# vme_can_vme_2.net
KiCad netlist of a schematic drawn in Altium Designer
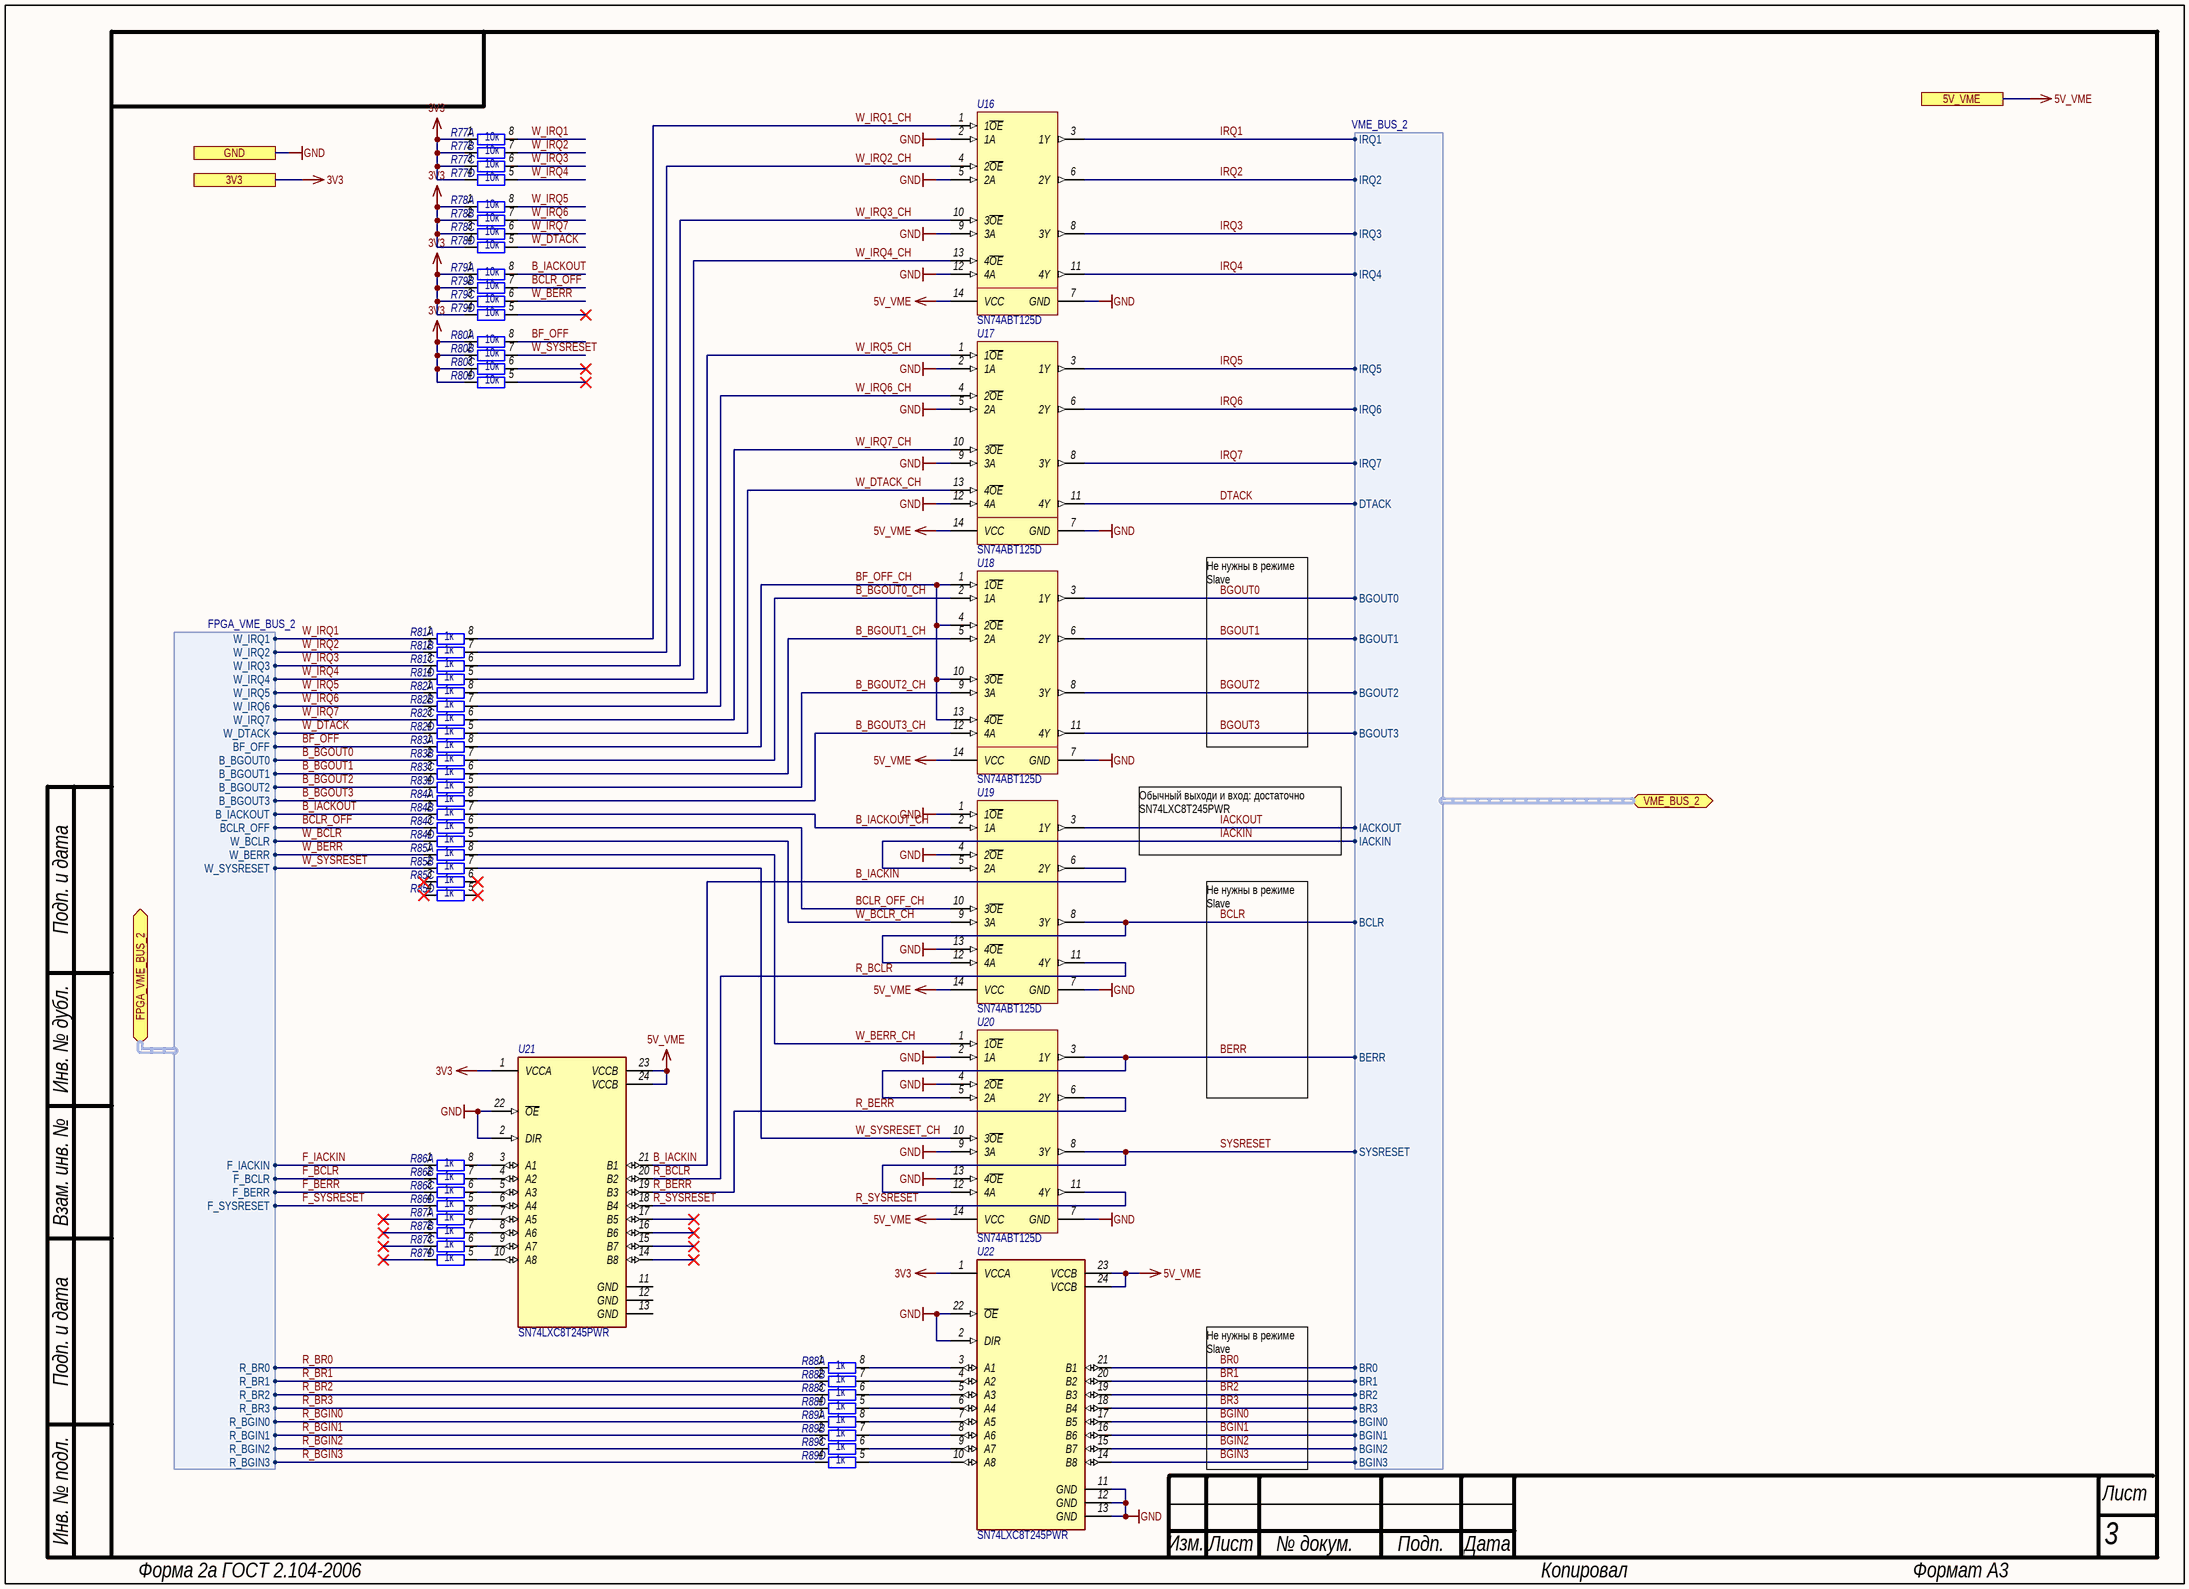
[diagram p0: vme_can_vme_2.SchDoc]

(export (version "E")
  (design (tool "Eeschema 10.0.6"))
  (components
    (comp (ref "R77")
      (value "10к")
      (footprint "TC124")
      (description "4 Chip Resistor Array")
      (libsource (lib "Passive") (part "Resistor-4"))
    )
    (comp (ref "R78")
      (value "10к")
      (footprint "TC124")
      (description "4 Chip Resistor Array")
      (libsource (lib "Passive") (part "Resistor-4"))
    )
    (comp (ref "R79")
      (value "10к")
      (footprint "TC124")
      (description "4 Chip Resistor Array")
      (libsource (lib "Passive") (part "Resistor-4"))
    )
    (comp (ref "R80")
      (value "10к")
      (footprint "TC124")
      (description "4 Chip Resistor Array")
      (libsource (lib "Passive") (part "Resistor-4"))
    )
    (comp (ref "R81")
      (value "1к")
      (footprint "TC124")
      (description "4 Chip Resistor Array")
      (libsource (lib "Passive") (part "Resistor-4"))
    )
    (comp (ref "R82")
      (value "1к")
      (footprint "TC124")
      (description "4 Chip Resistor Array")
      (libsource (lib "Passive") (part "Resistor-4"))
    )
    (comp (ref "R83")
      (value "1к")
      (footprint "TC124")
      (description "4 Chip Resistor Array")
      (libsource (lib "Passive") (part "Resistor-4"))
    )
    (comp (ref "R84")
      (value "1к")
      (footprint "TC124")
      (description "4 Chip Resistor Array")
      (libsource (lib "Passive") (part "Resistor-4"))
    )
    (comp (ref "R85")
      (value "1к")
      (footprint "TC124")
      (description "4 Chip Resistor Array")
      (libsource (lib "Passive") (part "Resistor-4"))
    )
    (comp (ref "R86")
      (value "1к")
      (footprint "TC124")
      (description "4 Chip Resistor Array")
      (libsource (lib "Passive") (part "Resistor-4"))
    )
    (comp (ref "R87")
      (value "1к")
      (footprint "TC124")
      (description "4 Chip Resistor Array")
      (libsource (lib "Passive") (part "Resistor-4"))
    )
    (comp (ref "R88")
      (value "1к")
      (footprint "TC124")
      (description "4 Chip Resistor Array")
      (libsource (lib "Passive") (part "Resistor-4"))
    )
    (comp (ref "R89")
      (value "1к")
      (footprint "TC124")
      (description "4 Chip Resistor Array")
      (libsource (lib "Passive") (part "Resistor-4"))
    )
    (comp (ref "U16")
      (value "SN74ABT125D")
      (footprint "SOIC-14")
      (description "QUADRUPLE BUS BUFFER GATES")
      (fields (field (name "НАИМЕНОВАНИЕ") "SN74ABT125D"))
      (libsource (lib "Transceiver") (part "SN74ABT125D"))
    )
    (comp (ref "U17")
      (value "SN74ABT125D")
      (footprint "SOIC-14")
      (description "QUADRUPLE BUS BUFFER GATES")
      (fields (field (name "НАИМЕНОВАНИЕ") "SN74ABT125D"))
      (libsource (lib "Transceiver") (part "SN74ABT125D"))
    )
    (comp (ref "U18")
      (value "SN74ABT125D")
      (footprint "SOIC-14")
      (description "QUADRUPLE BUS BUFFER GATES")
      (fields (field (name "НАИМЕНОВАНИЕ") "SN74ABT125D"))
      (libsource (lib "Transceiver") (part "SN74ABT125D"))
    )
    (comp (ref "U19")
      (value "SN74ABT125D")
      (footprint "SOIC-14")
      (description "QUADRUPLE BUS BUFFER GATES")
      (fields (field (name "НАИМЕНОВАНИЕ") "SN74ABT125D"))
      (libsource (lib "Transceiver") (part "SN74ABT125D"))
    )
    (comp (ref "U20")
      (value "SN74ABT125D")
      (footprint "SOIC-14")
      (description "QUADRUPLE BUS BUFFER GATES")
      (fields (field (name "НАИМЕНОВАНИЕ") "SN74ABT125D"))
      (libsource (lib "Transceiver") (part "SN74ABT125D"))
    )
    (comp (ref "U21")
      (value "SN74LXC8T245PWR")
      (footprint "TSSOP-24")
      (description "Dual-Supply Bus Transceiver with Configurable Level Shifting\r\nand 3-State Outputs")
      (fields (field (name "НАИМЕНОВАНИЕ") "SN74LXC8T245PWR"))
      (libsource (lib "Transceiver") (part "SN74LXC8T245PWR"))
    )
    (comp (ref "U22")
      (value "SN74LXC8T245PWR")
      (footprint "TSSOP-24")
      (description "Dual-Supply Bus Transceiver with Configurable Level Shifting\r\nand 3-State Outputs")
      (fields (field (name "НАИМЕНОВАНИЕ") "SN74LXC8T245PWR"))
      (libsource (lib "Transceiver") (part "SN74LXC8T245PWR"))
    )
  )
  (nets
    (net (code "3") (name "/BCLR") (class "Default")
      (node (ref "U19") (pin "12") (pinfunction "4A_12") (pintype "input"))
      (node (ref "U19") (pin "8") (pinfunction "3Y_8") (pintype "output"))
    )
    (net (code "4") (name "/BCLR_OFF") (class "Default")
      (node (ref "R79") (pin "7") (pinfunction "7_7") (pintype "passive"))
      (node (ref "R84") (pin "3") (pinfunction "3_3") (pintype "passive"))
    )
    (net (code "5") (name "/BCLR_OFF_CH") (class "Default")
      (node (ref "R84") (pin "6") (pinfunction "6_6") (pintype "passive"))
      (node (ref "U19") (pin "10") (pinfunction "3~{OE}_10") (pintype "input"))
    )
    (net (code "6") (name "/BERR") (class "Default")
      (node (ref "U20") (pin "3") (pinfunction "1Y_3") (pintype "output"))
      (node (ref "U20") (pin "5") (pinfunction "2A_5") (pintype "input"))
    )
    (net (code "7") (name "/BF_OFF") (class "Default")
      (node (ref "R80") (pin "8") (pinfunction "8_8") (pintype "passive"))
      (node (ref "R83") (pin "1") (pinfunction "1_1") (pintype "passive"))
    )
    (net (code "8") (name "/BF_OFF_CH") (class "Default")
      (node (ref "R83") (pin "8") (pinfunction "8_8") (pintype "passive"))
      (node (ref "U18") (pin "1") (pinfunction "1~{OE}_1") (pintype "input"))
      (node (ref "U18") (pin "10") (pinfunction "3~{OE}_10") (pintype "input"))
      (node (ref "U18") (pin "13") (pinfunction "4~{OE}_13") (pintype "input"))
      (node (ref "U18") (pin "4") (pinfunction "2~{OE}_4") (pintype "input"))
    )
    (net (code "9") (name "/BGIN0") (class "Default")
      (node (ref "U22") (pin "17") (pinfunction "B5_17") (pintype "bidirectional"))
    )
    (net (code "10") (name "/BGIN1") (class "Default")
      (node (ref "U22") (pin "16") (pinfunction "B6_16") (pintype "bidirectional"))
    )
    (net (code "11") (name "/BGIN2") (class "Default")
      (node (ref "U22") (pin "15") (pinfunction "B7_15") (pintype "bidirectional"))
    )
    (net (code "12") (name "/BGIN3") (class "Default")
      (node (ref "U22") (pin "14") (pinfunction "B8_14") (pintype "bidirectional"))
    )
    (net (code "13") (name "/BGOUT0") (class "Default")
      (node (ref "U18") (pin "3") (pinfunction "1Y_3") (pintype "output"))
    )
    (net (code "14") (name "/BGOUT1") (class "Default")
      (node (ref "U18") (pin "6") (pinfunction "2Y_6") (pintype "output"))
    )
    (net (code "15") (name "/BGOUT2") (class "Default")
      (node (ref "U18") (pin "8") (pinfunction "3Y_8") (pintype "output"))
    )
    (net (code "16") (name "/BGOUT3") (class "Default")
      (node (ref "U18") (pin "11") (pinfunction "4Y_11") (pintype "output"))
    )
    (net (code "17") (name "/BR0") (class "Default")
      (node (ref "U22") (pin "21") (pinfunction "B1_21") (pintype "bidirectional"))
    )
    (net (code "18") (name "/BR1") (class "Default")
      (node (ref "U22") (pin "20") (pinfunction "B2_20") (pintype "bidirectional"))
    )
    (net (code "19") (name "/BR2") (class "Default")
      (node (ref "U22") (pin "19") (pinfunction "B3_19") (pintype "bidirectional"))
    )
    (net (code "20") (name "/BR3") (class "Default")
      (node (ref "U22") (pin "18") (pinfunction "B4_18") (pintype "bidirectional"))
    )
    (net (code "21") (name "/B_BGOUT0") (class "Default")
      (node (ref "R83") (pin "2") (pinfunction "2_2") (pintype "passive"))
    )
    (net (code "22") (name "/B_BGOUT0_CH") (class "Default")
      (node (ref "R83") (pin "7") (pinfunction "7_7") (pintype "passive"))
      (node (ref "U18") (pin "2") (pinfunction "1A_2") (pintype "input"))
    )
    (net (code "23") (name "/B_BGOUT1") (class "Default")
      (node (ref "R83") (pin "3") (pinfunction "3_3") (pintype "passive"))
    )
    (net (code "24") (name "/B_BGOUT1_CH") (class "Default")
      (node (ref "R83") (pin "6") (pinfunction "6_6") (pintype "passive"))
      (node (ref "U18") (pin "5") (pinfunction "2A_5") (pintype "input"))
    )
    (net (code "25") (name "/B_BGOUT2") (class "Default")
      (node (ref "R83") (pin "4") (pinfunction "4_4") (pintype "passive"))
    )
    (net (code "26") (name "/B_BGOUT2_CH") (class "Default")
      (node (ref "R83") (pin "5") (pinfunction "5_5") (pintype "passive"))
      (node (ref "U18") (pin "9") (pinfunction "3A_9") (pintype "input"))
    )
    (net (code "27") (name "/B_BGOUT3") (class "Default")
      (node (ref "R84") (pin "1") (pinfunction "1_1") (pintype "passive"))
    )
    (net (code "28") (name "/B_BGOUT3_CH") (class "Default")
      (node (ref "R84") (pin "8") (pinfunction "8_8") (pintype "passive"))
      (node (ref "U18") (pin "12") (pinfunction "4A_12") (pintype "input"))
    )
    (net (code "29") (name "/B_IACKIN") (class "Default")
      (node (ref "U19") (pin "6") (pinfunction "2Y_6") (pintype "output"))
      (node (ref "U21") (pin "21") (pinfunction "B1_21") (pintype "bidirectional"))
    )
    (net (code "30") (name "/B_IACKOUT") (class "Default")
      (node (ref "R79") (pin "8") (pinfunction "8_8") (pintype "passive"))
      (node (ref "R84") (pin "2") (pinfunction "2_2") (pintype "passive"))
    )
    (net (code "31") (name "/B_IACKOUT_CH") (class "Default")
      (node (ref "R84") (pin "7") (pinfunction "7_7") (pintype "passive"))
      (node (ref "U19") (pin "2") (pinfunction "1A_2") (pintype "input"))
    )
    (net (code "32") (name "/DTACK") (class "Default")
      (node (ref "U17") (pin "11") (pinfunction "4Y_11") (pintype "output"))
    )
    (net (code "33") (name "/F_BCLR") (class "Default")
      (node (ref "R86") (pin "2") (pinfunction "2_2") (pintype "passive"))
    )
    (net (code "34") (name "/F_BERR") (class "Default")
      (node (ref "R86") (pin "3") (pinfunction "3_3") (pintype "passive"))
    )
    (net (code "35") (name "/F_IACKIN") (class "Default")
      (node (ref "R86") (pin "1") (pinfunction "1_1") (pintype "passive"))
    )
    (net (code "36") (name "/F_SYSRESET") (class "Default")
      (node (ref "R86") (pin "4") (pinfunction "4_4") (pintype "passive"))
    )
    (net (code "37") (name "/IACKIN") (class "Default")
      (node (ref "U19") (pin "5") (pinfunction "2A_5") (pintype "input"))
    )
    (net (code "38") (name "/IACKOUT") (class "Default")
      (node (ref "U19") (pin "3") (pinfunction "1Y_3") (pintype "output"))
    )
    (net (code "39") (name "/IRQ1") (class "Default")
      (node (ref "U16") (pin "3") (pinfunction "1Y_3") (pintype "output"))
    )
    (net (code "40") (name "/IRQ2") (class "Default")
      (node (ref "U16") (pin "6") (pinfunction "2Y_6") (pintype "output"))
    )
    (net (code "41") (name "/IRQ3") (class "Default")
      (node (ref "U16") (pin "8") (pinfunction "3Y_8") (pintype "output"))
    )
    (net (code "42") (name "/IRQ4") (class "Default")
      (node (ref "U16") (pin "11") (pinfunction "4Y_11") (pintype "output"))
    )
    (net (code "43") (name "/IRQ5") (class "Default")
      (node (ref "U17") (pin "3") (pinfunction "1Y_3") (pintype "output"))
    )
    (net (code "44") (name "/IRQ6") (class "Default")
      (node (ref "U17") (pin "6") (pinfunction "2Y_6") (pintype "output"))
    )
    (net (code "45") (name "/IRQ7") (class "Default")
      (node (ref "U17") (pin "8") (pinfunction "3Y_8") (pintype "output"))
    )
    (net (code "46") (name "/R_BCLR") (class "Default")
      (node (ref "U19") (pin "11") (pinfunction "4Y_11") (pintype "output"))
      (node (ref "U21") (pin "20") (pinfunction "B2_20") (pintype "bidirectional"))
    )
    (net (code "47") (name "/R_BERR") (class "Default")
      (node (ref "U20") (pin "6") (pinfunction "2Y_6") (pintype "output"))
      (node (ref "U21") (pin "19") (pinfunction "B3_19") (pintype "bidirectional"))
    )
    (net (code "48") (name "/R_BGIN0") (class "Default")
      (node (ref "R89") (pin "1") (pinfunction "1_1") (pintype "passive"))
    )
    (net (code "49") (name "/R_BGIN1") (class "Default")
      (node (ref "R89") (pin "2") (pinfunction "2_2") (pintype "passive"))
    )
    (net (code "50") (name "/R_BGIN2") (class "Default")
      (node (ref "R89") (pin "3") (pinfunction "3_3") (pintype "passive"))
    )
    (net (code "51") (name "/R_BGIN3") (class "Default")
      (node (ref "R89") (pin "4") (pinfunction "4_4") (pintype "passive"))
    )
    (net (code "52") (name "/R_BR0") (class "Default")
      (node (ref "R88") (pin "1") (pinfunction "1_1") (pintype "passive"))
    )
    (net (code "53") (name "/R_BR1") (class "Default")
      (node (ref "R88") (pin "2") (pinfunction "2_2") (pintype "passive"))
    )
    (net (code "54") (name "/R_BR2") (class "Default")
      (node (ref "R88") (pin "3") (pinfunction "3_3") (pintype "passive"))
    )
    (net (code "55") (name "/R_BR3") (class "Default")
      (node (ref "R88") (pin "4") (pinfunction "4_4") (pintype "passive"))
    )
    (net (code "56") (name "/R_SYSRESET") (class "Default")
      (node (ref "U20") (pin "11") (pinfunction "4Y_11") (pintype "output"))
      (node (ref "U21") (pin "18") (pinfunction "B4_18") (pintype "bidirectional"))
    )
    (net (code "57") (name "/SYSRESET") (class "Default")
      (node (ref "U20") (pin "12") (pinfunction "4A_12") (pintype "input"))
      (node (ref "U20") (pin "8") (pinfunction "3Y_8") (pintype "output"))
    )
    (net (code "58") (name "/W_BCLR") (class "Default")
      (node (ref "R84") (pin "4") (pinfunction "4_4") (pintype "passive"))
    )
    (net (code "59") (name "/W_BCLR_CH") (class "Default")
      (node (ref "R84") (pin "5") (pinfunction "5_5") (pintype "passive"))
      (node (ref "U19") (pin "9") (pinfunction "3A_9") (pintype "input"))
    )
    (net (code "60") (name "/W_BERR") (class "Default")
      (node (ref "R79") (pin "6") (pinfunction "6_6") (pintype "passive"))
      (node (ref "R85") (pin "1") (pinfunction "1_1") (pintype "passive"))
    )
    (net (code "61") (name "/W_BERR_CH") (class "Default")
      (node (ref "R85") (pin "8") (pinfunction "8_8") (pintype "passive"))
      (node (ref "U20") (pin "1") (pinfunction "1~{OE}_1") (pintype "input"))
    )
    (net (code "62") (name "/W_DTACK") (class "Default")
      (node (ref "R78") (pin "5") (pinfunction "5_5") (pintype "passive"))
      (node (ref "R82") (pin "4") (pinfunction "4_4") (pintype "passive"))
    )
    (net (code "63") (name "/W_DTACK_CH") (class "Default")
      (node (ref "R82") (pin "5") (pinfunction "5_5") (pintype "passive"))
      (node (ref "U17") (pin "13") (pinfunction "4~{OE}_13") (pintype "input"))
    )
    (net (code "64") (name "/W_IRQ1") (class "Default")
      (node (ref "R77") (pin "8") (pinfunction "8_8") (pintype "passive"))
      (node (ref "R81") (pin "1") (pinfunction "1_1") (pintype "passive"))
    )
    (net (code "65") (name "/W_IRQ1_CH") (class "Default")
      (node (ref "R81") (pin "8") (pinfunction "8_8") (pintype "passive"))
      (node (ref "U16") (pin "1") (pinfunction "1~{OE}_1") (pintype "input"))
    )
    (net (code "66") (name "/W_IRQ2") (class "Default")
      (node (ref "R77") (pin "7") (pinfunction "7_7") (pintype "passive"))
      (node (ref "R81") (pin "2") (pinfunction "2_2") (pintype "passive"))
    )
    (net (code "67") (name "/W_IRQ2_CH") (class "Default")
      (node (ref "R81") (pin "7") (pinfunction "7_7") (pintype "passive"))
      (node (ref "U16") (pin "4") (pinfunction "2~{OE}_4") (pintype "input"))
    )
    (net (code "68") (name "/W_IRQ3") (class "Default")
      (node (ref "R77") (pin "6") (pinfunction "6_6") (pintype "passive"))
      (node (ref "R81") (pin "3") (pinfunction "3_3") (pintype "passive"))
    )
    (net (code "69") (name "/W_IRQ3_CH") (class "Default")
      (node (ref "R81") (pin "6") (pinfunction "6_6") (pintype "passive"))
      (node (ref "U16") (pin "10") (pinfunction "3~{OE}_10") (pintype "input"))
    )
    (net (code "70") (name "/W_IRQ4") (class "Default")
      (node (ref "R77") (pin "5") (pinfunction "5_5") (pintype "passive"))
      (node (ref "R81") (pin "4") (pinfunction "4_4") (pintype "passive"))
    )
    (net (code "71") (name "/W_IRQ4_CH") (class "Default")
      (node (ref "R81") (pin "5") (pinfunction "5_5") (pintype "passive"))
      (node (ref "U16") (pin "13") (pinfunction "4~{OE}_13") (pintype "input"))
    )
    (net (code "72") (name "/W_IRQ5") (class "Default")
      (node (ref "R78") (pin "8") (pinfunction "8_8") (pintype "passive"))
      (node (ref "R82") (pin "1") (pinfunction "1_1") (pintype "passive"))
    )
    (net (code "73") (name "/W_IRQ5_CH") (class "Default")
      (node (ref "R82") (pin "8") (pinfunction "8_8") (pintype "passive"))
      (node (ref "U17") (pin "1") (pinfunction "1~{OE}_1") (pintype "input"))
    )
    (net (code "74") (name "/W_IRQ6") (class "Default")
      (node (ref "R78") (pin "7") (pinfunction "7_7") (pintype "passive"))
      (node (ref "R82") (pin "2") (pinfunction "2_2") (pintype "passive"))
    )
    (net (code "75") (name "/W_IRQ6_CH") (class "Default")
      (node (ref "R82") (pin "7") (pinfunction "7_7") (pintype "passive"))
      (node (ref "U17") (pin "4") (pinfunction "2~{OE}_4") (pintype "input"))
    )
    (net (code "76") (name "/W_IRQ7") (class "Default")
      (node (ref "R78") (pin "6") (pinfunction "6_6") (pintype "passive"))
      (node (ref "R82") (pin "3") (pinfunction "3_3") (pintype "passive"))
    )
    (net (code "77") (name "/W_IRQ7_CH") (class "Default")
      (node (ref "R82") (pin "6") (pinfunction "6_6") (pintype "passive"))
      (node (ref "U17") (pin "10") (pinfunction "3~{OE}_10") (pintype "input"))
    )
    (net (code "78") (name "/W_SYSRESET") (class "Default")
      (node (ref "R80") (pin "7") (pinfunction "7_7") (pintype "passive"))
      (node (ref "R85") (pin "2") (pinfunction "2_2") (pintype "passive"))
    )
    (net (code "79") (name "/W_SYSRESET_CH") (class "Default")
      (node (ref "R85") (pin "7") (pinfunction "7_7") (pintype "passive"))
      (node (ref "U20") (pin "10") (pinfunction "3~{OE}_10") (pintype "input"))
    )
    (net (code "82") (name "3V3") (class "Default")
      (node (ref "R77") (pin "1") (pinfunction "1_1") (pintype "passive"))
      (node (ref "R77") (pin "2") (pinfunction "2_2") (pintype "passive"))
      (node (ref "R77") (pin "3") (pinfunction "3_3") (pintype "passive"))
      (node (ref "R77") (pin "4") (pinfunction "4_4") (pintype "passive"))
      (node (ref "R78") (pin "1") (pinfunction "1_1") (pintype "passive"))
      (node (ref "R78") (pin "2") (pinfunction "2_2") (pintype "passive"))
      (node (ref "R78") (pin "3") (pinfunction "3_3") (pintype "passive"))
      (node (ref "R78") (pin "4") (pinfunction "4_4") (pintype "passive"))
      (node (ref "R79") (pin "1") (pinfunction "1_1") (pintype "passive"))
      (node (ref "R79") (pin "2") (pinfunction "2_2") (pintype "passive"))
      (node (ref "R79") (pin "3") (pinfunction "3_3") (pintype "passive"))
      (node (ref "R79") (pin "4") (pinfunction "4_4") (pintype "passive"))
      (node (ref "R80") (pin "1") (pinfunction "1_1") (pintype "passive"))
      (node (ref "R80") (pin "2") (pinfunction "2_2") (pintype "passive"))
      (node (ref "R80") (pin "3") (pinfunction "3_3") (pintype "passive"))
      (node (ref "R80") (pin "4") (pinfunction "4_4") (pintype "passive"))
      (node (ref "U21") (pin "1") (pinfunction "VCCA_1") (pintype "power_in"))
      (node (ref "U22") (pin "1") (pinfunction "VCCA_1") (pintype "power_in"))
    )
    (net (code "83") (name "5V_VME") (class "Default")
      (node (ref "U16") (pin "14") (pinfunction "VCC_14") (pintype "power_in"))
      (node (ref "U17") (pin "14") (pinfunction "VCC_14") (pintype "power_in"))
      (node (ref "U18") (pin "14") (pinfunction "VCC_14") (pintype "power_in"))
      (node (ref "U19") (pin "14") (pinfunction "VCC_14") (pintype "power_in"))
      (node (ref "U20") (pin "14") (pinfunction "VCC_14") (pintype "power_in"))
      (node (ref "U21") (pin "23") (pinfunction "VCCB_23") (pintype "power_in"))
      (node (ref "U21") (pin "24") (pinfunction "VCCB_24") (pintype "power_in"))
      (node (ref "U22") (pin "23") (pinfunction "VCCB_23") (pintype "power_in"))
      (node (ref "U22") (pin "24") (pinfunction "VCCB_24") (pintype "power_in"))
    )
    (net (code "84") (name "GND") (class "Default")
      (node (ref "U16") (pin "12") (pinfunction "4A_12") (pintype "input"))
      (node (ref "U16") (pin "2") (pinfunction "1A_2") (pintype "input"))
      (node (ref "U16") (pin "5") (pinfunction "2A_5") (pintype "input"))
      (node (ref "U16") (pin "7") (pinfunction "GND_7") (pintype "power_in"))
      (node (ref "U16") (pin "9") (pinfunction "3A_9") (pintype "input"))
      (node (ref "U17") (pin "12") (pinfunction "4A_12") (pintype "input"))
      (node (ref "U17") (pin "2") (pinfunction "1A_2") (pintype "input"))
      (node (ref "U17") (pin "5") (pinfunction "2A_5") (pintype "input"))
      (node (ref "U17") (pin "7") (pinfunction "GND_7") (pintype "power_in"))
      (node (ref "U17") (pin "9") (pinfunction "3A_9") (pintype "input"))
      (node (ref "U18") (pin "7") (pinfunction "GND_7") (pintype "power_in"))
      (node (ref "U19") (pin "1") (pinfunction "1~{OE}_1") (pintype "input"))
      (node (ref "U19") (pin "13") (pinfunction "4~{OE}_13") (pintype "input"))
      (node (ref "U19") (pin "4") (pinfunction "2~{OE}_4") (pintype "input"))
      (node (ref "U19") (pin "7") (pinfunction "GND_7") (pintype "power_in"))
      (node (ref "U20") (pin "13") (pinfunction "4~{OE}_13") (pintype "input"))
      (node (ref "U20") (pin "2") (pinfunction "1A_2") (pintype "input"))
      (node (ref "U20") (pin "4") (pinfunction "2~{OE}_4") (pintype "input"))
      (node (ref "U20") (pin "7") (pinfunction "GND_7") (pintype "power_in"))
      (node (ref "U20") (pin "9") (pinfunction "3A_9") (pintype "input"))
      (node (ref "U21") (pin "2") (pinfunction "DIR_2") (pintype "input"))
      (node (ref "U21") (pin "22") (pinfunction "~{OE}_22") (pintype "input"))
      (node (ref "U22") (pin "11") (pinfunction "GND_11") (pintype "power_in"))
      (node (ref "U22") (pin "12") (pinfunction "GND_12") (pintype "power_in"))
      (node (ref "U22") (pin "13") (pinfunction "GND_13") (pintype "power_in"))
      (node (ref "U22") (pin "2") (pinfunction "DIR_2") (pintype "input"))
      (node (ref "U22") (pin "22") (pinfunction "~{OE}_22") (pintype "input"))
    )
    (net (code "85") (name "Net-(U21-A1)") (class "Default")
      (node (ref "R86") (pin "8") (pinfunction "8_8") (pintype "passive"))
      (node (ref "U21") (pin "3") (pinfunction "A1_3") (pintype "bidirectional"))
    )
    (net (code "86") (name "Net-(U21-A2)") (class "Default")
      (node (ref "R86") (pin "7") (pinfunction "7_7") (pintype "passive"))
      (node (ref "U21") (pin "4") (pinfunction "A2_4") (pintype "bidirectional"))
    )
    (net (code "87") (name "Net-(U21-A3)") (class "Default")
      (node (ref "R86") (pin "6") (pinfunction "6_6") (pintype "passive"))
      (node (ref "U21") (pin "5") (pinfunction "A3_5") (pintype "bidirectional"))
    )
    (net (code "88") (name "Net-(U21-A4)") (class "Default")
      (node (ref "R86") (pin "5") (pinfunction "5_5") (pintype "passive"))
      (node (ref "U21") (pin "6") (pinfunction "A4_6") (pintype "bidirectional"))
    )
    (net (code "89") (name "Net-(U21-A5)") (class "Default")
      (node (ref "R87") (pin "8") (pinfunction "8_8") (pintype "passive"))
      (node (ref "U21") (pin "7") (pinfunction "A5_7") (pintype "bidirectional"))
    )
    (net (code "90") (name "Net-(U21-A6)") (class "Default")
      (node (ref "R87") (pin "7") (pinfunction "7_7") (pintype "passive"))
      (node (ref "U21") (pin "8") (pinfunction "A6_8") (pintype "bidirectional"))
    )
    (net (code "91") (name "Net-(U21-A7)") (class "Default")
      (node (ref "R87") (pin "6") (pinfunction "6_6") (pintype "passive"))
      (node (ref "U21") (pin "9") (pinfunction "A7_9") (pintype "bidirectional"))
    )
    (net (code "92") (name "Net-(U21-A8)") (class "Default")
      (node (ref "R87") (pin "5") (pinfunction "5_5") (pintype "passive"))
      (node (ref "U21") (pin "10") (pinfunction "A8_10") (pintype "bidirectional"))
    )
    (net (code "93") (name "Net-(U22-A1)") (class "Default")
      (node (ref "R88") (pin "8") (pinfunction "8_8") (pintype "passive"))
      (node (ref "U22") (pin "3") (pinfunction "A1_3") (pintype "bidirectional"))
    )
    (net (code "94") (name "Net-(U22-A2)") (class "Default")
      (node (ref "R88") (pin "7") (pinfunction "7_7") (pintype "passive"))
      (node (ref "U22") (pin "4") (pinfunction "A2_4") (pintype "bidirectional"))
    )
    (net (code "95") (name "Net-(U22-A3)") (class "Default")
      (node (ref "R88") (pin "6") (pinfunction "6_6") (pintype "passive"))
      (node (ref "U22") (pin "5") (pinfunction "A3_5") (pintype "bidirectional"))
    )
    (net (code "96") (name "Net-(U22-A4)") (class "Default")
      (node (ref "R88") (pin "5") (pinfunction "5_5") (pintype "passive"))
      (node (ref "U22") (pin "6") (pinfunction "A4_6") (pintype "bidirectional"))
    )
    (net (code "97") (name "Net-(U22-A5)") (class "Default")
      (node (ref "R89") (pin "8") (pinfunction "8_8") (pintype "passive"))
      (node (ref "U22") (pin "7") (pinfunction "A5_7") (pintype "bidirectional"))
    )
    (net (code "98") (name "Net-(U22-A6)") (class "Default")
      (node (ref "R89") (pin "7") (pinfunction "7_7") (pintype "passive"))
      (node (ref "U22") (pin "8") (pinfunction "A6_8") (pintype "bidirectional"))
    )
    (net (code "99") (name "Net-(U22-A7)") (class "Default")
      (node (ref "R89") (pin "6") (pinfunction "6_6") (pintype "passive"))
      (node (ref "U22") (pin "9") (pinfunction "A7_9") (pintype "bidirectional"))
    )
    (net (code "100") (name "Net-(U22-A8)") (class "Default")
      (node (ref "R89") (pin "5") (pinfunction "5_5") (pintype "passive"))
      (node (ref "U22") (pin "10") (pinfunction "A8_10") (pintype "bidirectional"))
    )
    (net (code "101") (name "unconnected-(R79-Pad5)") (class "Default")
      (node (ref "R79") (pin "5") (pinfunction "5_5") (pintype "passive+no_connect"))
    )
    (net (code "102") (name "unconnected-(R80-Pad5)") (class "Default")
      (node (ref "R80") (pin "5") (pinfunction "5_5") (pintype "passive+no_connect"))
    )
    (net (code "103") (name "unconnected-(R80-Pad6)") (class "Default")
      (node (ref "R80") (pin "6") (pinfunction "6_6") (pintype "passive+no_connect"))
    )
    (net (code "104") (name "unconnected-(R85-Pad3)") (class "Default")
      (node (ref "R85") (pin "3") (pinfunction "3_3") (pintype "passive+no_connect"))
    )
    (net (code "105") (name "unconnected-(R85-Pad4)") (class "Default")
      (node (ref "R85") (pin "4") (pinfunction "4_4") (pintype "passive+no_connect"))
    )
    (net (code "106") (name "unconnected-(R85-Pad5)") (class "Default")
      (node (ref "R85") (pin "5") (pinfunction "5_5") (pintype "passive+no_connect"))
    )
    (net (code "107") (name "unconnected-(R85-Pad6)") (class "Default")
      (node (ref "R85") (pin "6") (pinfunction "6_6") (pintype "passive+no_connect"))
    )
    (net (code "108") (name "unconnected-(R87-Pad1)") (class "Default")
      (node (ref "R87") (pin "1") (pinfunction "1_1") (pintype "passive+no_connect"))
    )
    (net (code "109") (name "unconnected-(R87-Pad2)") (class "Default")
      (node (ref "R87") (pin "2") (pinfunction "2_2") (pintype "passive+no_connect"))
    )
    (net (code "110") (name "unconnected-(R87-Pad3)") (class "Default")
      (node (ref "R87") (pin "3") (pinfunction "3_3") (pintype "passive+no_connect"))
    )
    (net (code "111") (name "unconnected-(R87-Pad4)") (class "Default")
      (node (ref "R87") (pin "4") (pinfunction "4_4") (pintype "passive+no_connect"))
    )
    (net (code "112") (name "unconnected-(U21-B5-Pad17)") (class "Default")
      (node (ref "U21") (pin "17") (pinfunction "B5_17") (pintype "bidirectional+no_connect"))
    )
    (net (code "113") (name "unconnected-(U21-B6-Pad16)") (class "Default")
      (node (ref "U21") (pin "16") (pinfunction "B6_16") (pintype "bidirectional+no_connect"))
    )
    (net (code "114") (name "unconnected-(U21-B7-Pad15)") (class "Default")
      (node (ref "U21") (pin "15") (pinfunction "B7_15") (pintype "bidirectional+no_connect"))
    )
    (net (code "115") (name "unconnected-(U21-B8-Pad14)") (class "Default")
      (node (ref "U21") (pin "14") (pinfunction "B8_14") (pintype "bidirectional+no_connect"))
    )
    (net (code "116") (name "unconnected-(U21-GND-Pad11)") (class "Default")
      (node (ref "U21") (pin "11") (pinfunction "GND_11") (pintype "power_in"))
    )
    (net (code "117") (name "unconnected-(U21-GND-Pad12)") (class "Default")
      (node (ref "U21") (pin "12") (pinfunction "GND_12") (pintype "power_in"))
    )
    (net (code "118") (name "unconnected-(U21-GND-Pad13)") (class "Default")
      (node (ref "U21") (pin "13") (pinfunction "GND_13") (pintype "power_in"))
    )
  )
)
